# MT29F1G01ABAFDWB_QSPI_NAND_Flash.net
KiCad netlist of a schematic drawn in Altium Designer
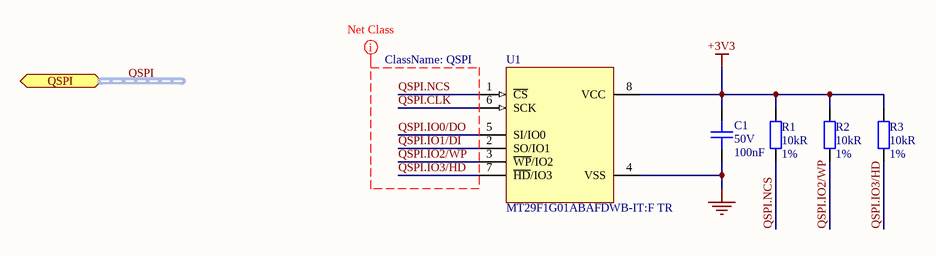
[diagram p0: MT29F1G01ABAFDWB_QSPI_NAND_Flash.SchDoc]

(export (version "E")
  (design (tool "Eeschema 10.0.6"))
  (components
    (comp (ref "C1")
      (value "CAP CER 0.1UF 50V X7R 0402")
      (footprint "C0402")
      (description "0.1µF ±10% 50V Ceramic Capacitor X7R 0402 (1005 Metric)")
      (fields
        (field (name "MANUFACTURER PART NUMBER") "CGA2B3X7R1H104K050BB")
        (field (name "MANUFACTURER") "TDK")
        (field (name "VOLTAGE") "50V")
        (field (name "CAPACITANCE") "100nF")
      )
      (libsource (lib "capacitors_smd") (part "CAP CER 0.1UF 50V X7R 0402"))
    )
    (comp (ref "R1")
      (value "RES SMD 10K OHM 1% 1/16W 0402")
      (footprint "R0402")
      (description "10 kOhms ±1% 0.063W, 1/16W Chip Resistor 0402 (1005 Metric) Moisture Resistant Thick Film")
      (fields
        (field (name "MANUFACTURER PART NUMBER") "RC0402FR-0710KP")
        (field (name "MANUFACTURER") "Yageo")
        (field (name "RESISTANCE") "10kR")
        (field (name "TOLERANCE") "1%")
      )
      (libsource (lib "resistors_smd") (part "RES SMD 10K OHM 1% 1/16W 0402"))
    )
    (comp (ref "R2")
      (value "RES SMD 10K OHM 1% 1/16W 0402")
      (footprint "R0402")
      (description "10 kOhms ±1% 0.063W, 1/16W Chip Resistor 0402 (1005 Metric) Moisture Resistant Thick Film")
      (fields
        (field (name "MANUFACTURER PART NUMBER") "RC0402FR-0710KP")
        (field (name "MANUFACTURER") "Yageo")
        (field (name "RESISTANCE") "10kR")
        (field (name "TOLERANCE") "1%")
      )
      (libsource (lib "resistors_smd") (part "RES SMD 10K OHM 1% 1/16W 0402"))
    )
    (comp (ref "R3")
      (value "RES SMD 10K OHM 1% 1/16W 0402")
      (footprint "R0402")
      (description "10 kOhms ±1% 0.063W, 1/16W Chip Resistor 0402 (1005 Metric) Moisture Resistant Thick Film")
      (fields
        (field (name "MANUFACTURER PART NUMBER") "RC0402FR-0710KP")
        (field (name "MANUFACTURER") "Yageo")
        (field (name "RESISTANCE") "10kR")
        (field (name "TOLERANCE") "1%")
      )
      (libsource (lib "resistors_smd") (part "RES SMD 10K OHM 1% 1/16W 0402"))
    )
    (comp (ref "U1")
      (value "MT29F1G01ABAFDWB-IT:F TR")
      (footprint "U-PDFN-8_8X6_P127")
      (description "FLASH - NAND Memory IC 1Gb (1G x 1) SPI   8-U-PDFN (8x6)")
      (fields (field (name "MANUFACTURER") "Micron Technology"))
      (libsource (lib "BLDC_Motor_Driver") (part "IC MT29F1G01ABAFDWB FLASH 1GBIT SPI 8UPDFN"))
    )
  )
  (nets
    (net (code "2") (name "+3V3") (class "Default")
      (node (ref "C1") (pin "2") (pinfunction "2_2") (pintype "passive"))
      (node (ref "R1") (pin "1") (pinfunction "1_1") (pintype "passive"))
      (node (ref "R2") (pin "1") (pinfunction "1_1") (pintype "passive"))
      (node (ref "R3") (pin "1") (pinfunction "1_1") (pintype "passive"))
      (node (ref "U1") (pin "8") (pinfunction "VCC_8") (pintype "passive"))
    )
    (net (code "3") (name "/QSPI.CLK") (class "Default")
      (node (ref "U1") (pin "6") (pinfunction "SCK_6") (pintype "input"))
    )
    (net (code "4") (name "/QSPI.IO0{slash}DO") (class "Default")
      (node (ref "U1") (pin "5") (pinfunction "SI/IO0_5") (pintype "passive"))
    )
    (net (code "5") (name "/QSPI.IO1{slash}DI") (class "Default")
      (node (ref "U1") (pin "2") (pinfunction "SO/IO1_2") (pintype "passive"))
    )
    (net (code "6") (name "/QSPI.IO2{slash}WP") (class "Default")
      (node (ref "R2") (pin "2") (pinfunction "2_2") (pintype "passive"))
      (node (ref "U1") (pin "3") (pinfunction "~{WP}/IO2_3") (pintype "passive"))
    )
    (net (code "7") (name "/QSPI.IO3{slash}HD") (class "Default")
      (node (ref "R3") (pin "2") (pinfunction "2_2") (pintype "passive"))
      (node (ref "U1") (pin "7") (pinfunction "~{HD}/IO3_7") (pintype "passive"))
    )
    (net (code "8") (name "/QSPI.NCS") (class "Default")
      (node (ref "R1") (pin "2") (pinfunction "2_2") (pintype "passive"))
      (node (ref "U1") (pin "1") (pinfunction "CS_1") (pintype "input"))
    )
    (net (code "10") (name "GND") (class "Default")
      (node (ref "C1") (pin "1") (pinfunction "1_1") (pintype "passive"))
      (node (ref "U1") (pin "4") (pinfunction "VSS_4") (pintype "passive"))
    )
  )
)
